# Solenoid.net
KiCad netlist of a schematic drawn in EAGLE
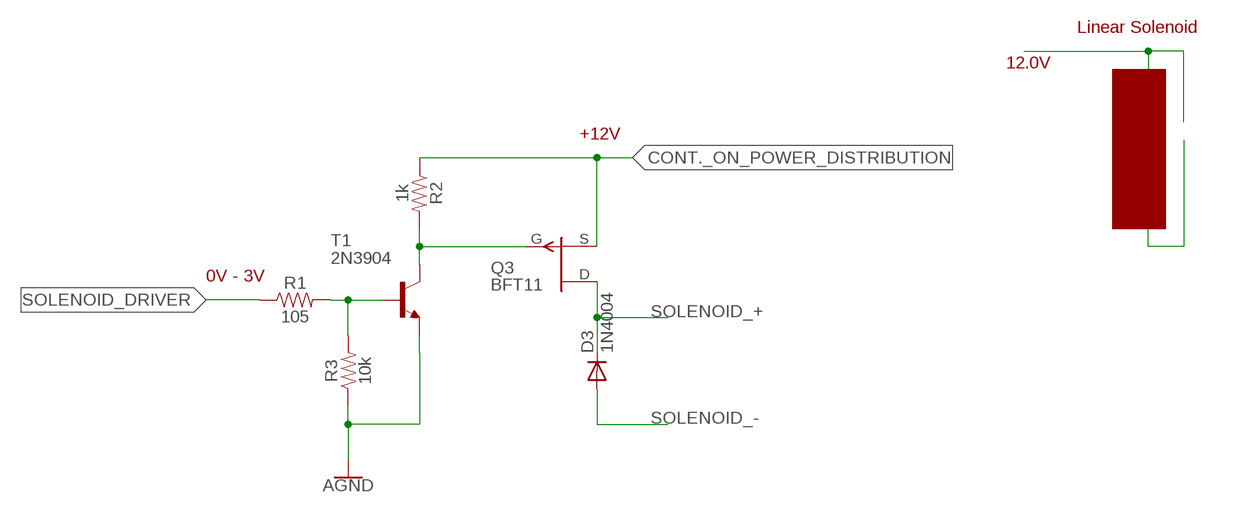
[diagram p0: schematic, sheet 1]

(export (version "E")
  (design (tool "Eeschema 10.0.6"))
  (components
    (comp (ref "D3")
      (value "1N4004")
      (footprint "eagle-import:DO41-10")
      (libsource (lib "eagle-import") (part "1N4004"))
    )
    (comp (ref "Q3")
      (value "BFT11")
      (footprint "eagle-import:TO92")
      (libsource (lib "eagle-import") (part "BFT11"))
    )
    (comp (ref "R1")
      (value "105")
      (footprint "eagle-import:0603")
      (libsource (lib "eagle-import") (part "105OHM-0603-1/10W-1%"))
    )
    (comp (ref "R2")
      (value "1k")
      (footprint "eagle-import:0603")
      (libsource (lib "eagle-import") (part "1KOHM-0603-1/10W-1%"))
    )
    (comp (ref "R3")
      (value "10k")
      (footprint "eagle-import:0603")
      (libsource (lib "eagle-import") (part "10KOHM-0603-1/10W-1%"))
    )
    (comp (ref "T1")
      (value "2N3904")
      (footprint "eagle-import:TO92")
      (libsource (lib "eagle-import") (part "2N3904"))
    )
  )
  (nets
    (net (code "1") (name "/SOLENOID_+") (class "Default")
      (node (ref "D3") (pin "C") (pinfunction "C_C") (pintype "passive"))
      (node (ref "Q3") (pin "1") (pinfunction "D_1") (pintype "passive"))
    )
    (net (code "2") (name "/SOLENOID_-") (class "Default")
      (node (ref "D3") (pin "A") (pinfunction "A_A") (pintype "passive"))
    )
    (net (code "3") (name "AGND") (class "Default")
      (node (ref "R3") (pin "1") (pinfunction "1_1") (pintype "passive"))
      (node (ref "T1") (pin "3") (pinfunction "E_3") (pintype "passive"))
    )
    (net (code "4") (name "CONT._ON_POWER_DISTRIBUTION") (class "Default")
      (node (ref "Q3") (pin "2") (pinfunction "S_2") (pintype "passive"))
      (node (ref "R2") (pin "1") (pinfunction "1_1") (pintype "passive"))
    )
    (net (code "5") (name "Net-(Q3-G)") (class "Default")
      (node (ref "Q3") (pin "3") (pinfunction "G_3") (pintype "passive"))
      (node (ref "R2") (pin "2") (pinfunction "2_2") (pintype "passive"))
      (node (ref "T1") (pin "1") (pinfunction "C_1") (pintype "passive"))
    )
    (net (code "6") (name "Net-(T1-B)") (class "Default")
      (node (ref "R1") (pin "2") (pinfunction "2_2") (pintype "passive"))
      (node (ref "R3") (pin "2") (pinfunction "2_2") (pintype "passive"))
      (node (ref "T1") (pin "2") (pinfunction "B_2") (pintype "passive"))
    )
    (net (code "7") (name "SOLENOID_DRIVER") (class "Default")
      (node (ref "R1") (pin "1") (pinfunction "1_1") (pintype "passive"))
    )
  )
)
